# Glue.net
KiCad netlist of a schematic drawn in Altium Designer
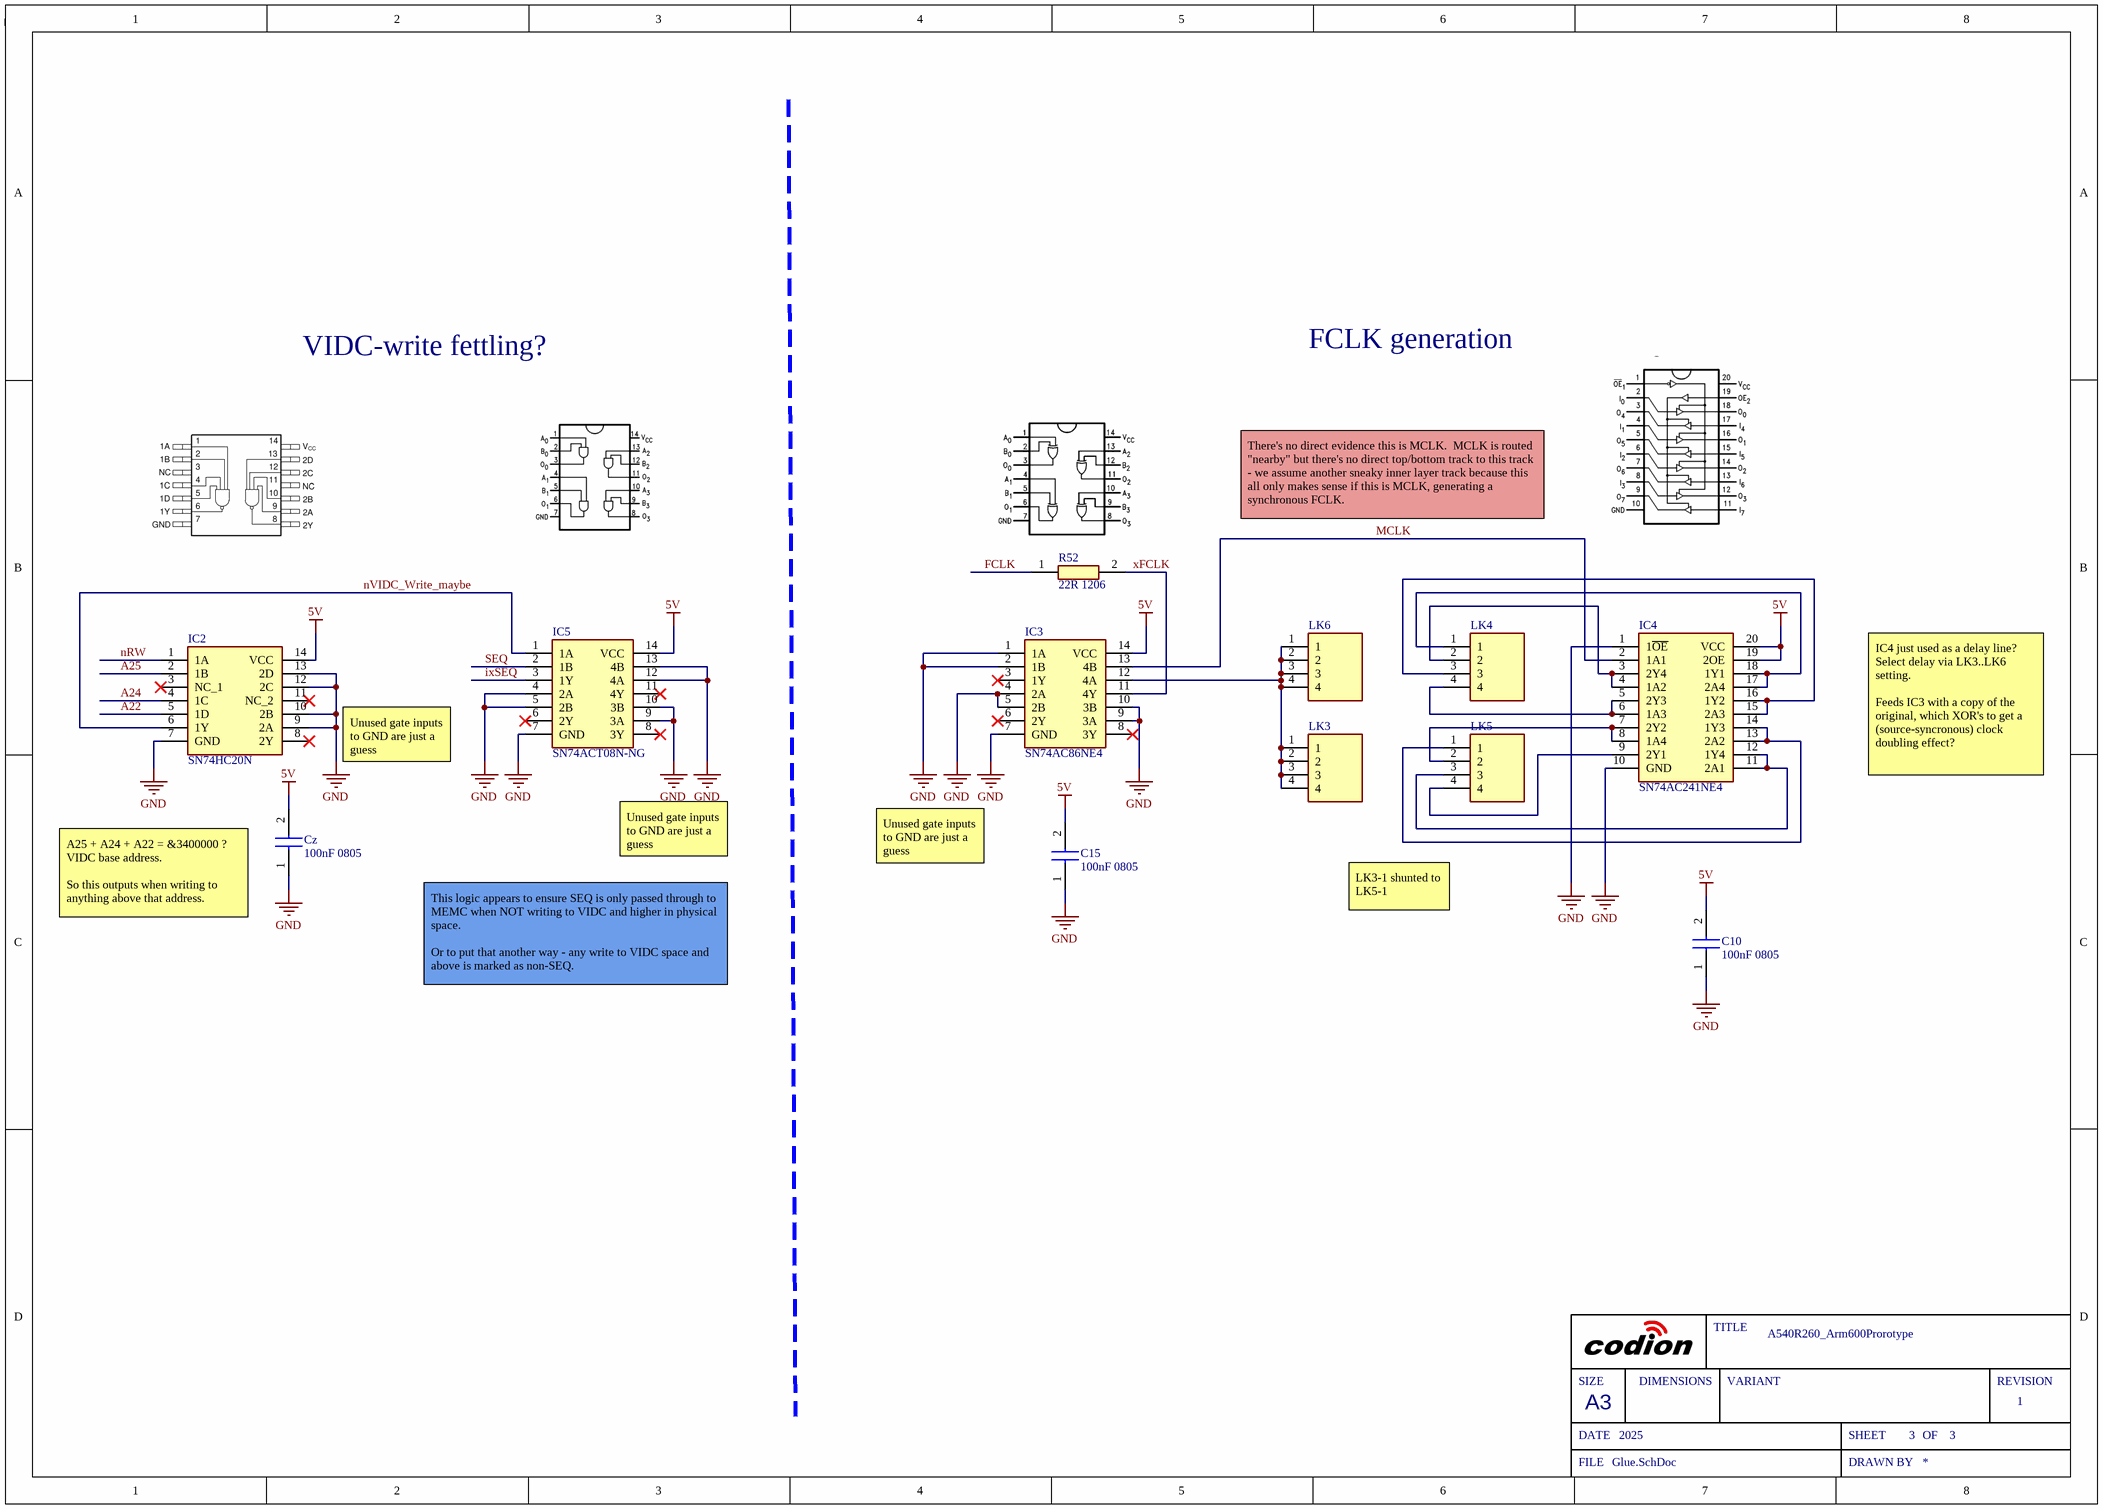
[diagram p0: Glue.SchDoc]

(export (version "E")
  (design (tool "Eeschema 10.0.6"))
  (components
    (comp (ref "C10")
      (value "100nF 0805")
      (footprint "SamacSys:CAPC2012X140N")
      (description "Capacitor")
      (fields
        (field (name "MANUFACTURER_PART_NUMBER") "C0805C104J4JACAUTO")
        (field (name "MOUSER PART NUMBER") "80-C0805C104J4JAUTO")
      )
      (libsource (lib "*") (part "C0805C104J4JACAUTO"))
    )
    (comp (ref "C15")
      (value "100nF 0805")
      (footprint "SamacSys:CAPC2012X140N")
      (description "Capacitor")
      (fields
        (field (name "MANUFACTURER_PART_NUMBER") "C0805C104J4JACAUTO")
        (field (name "MOUSER PART NUMBER") "80-C0805C104J4JAUTO")
      )
      (libsource (lib "*") (part "C0805C104J4JACAUTO"))
    )
    (comp (ref "Cz")
      (value "100nF 0805")
      (footprint "SamacSys:CAPC2012X140N")
      (description "Capacitor")
      (fields
        (field (name "MANUFACTURER_PART_NUMBER") "C0805C104J4JACAUTO")
        (field (name "MOUSER PART NUMBER") "80-C0805C104J4JAUTO")
      )
      (libsource (lib "*") (part "C0805C104J4JACAUTO"))
    )
    (comp (ref "IC2")
      (value "SN74HC20N")
      (footprint "SamacSys:DIP794W53P254L1930H508Q14N")
      (description "Integrated Circuit")
      (fields (field (name "MOUSER PART NUMBER") "595-SN74HC20N"))
      (libsource (lib "*") (part "SN74HC20N"))
    )
    (comp (ref "IC3")
      (value "SN74AC86NE4")
      (footprint "SamacSys:DIP794W53P254L1930H508Q14N")
      (description "Integrated Circuit")
      (libsource (lib "*") (part "SN74AC86NE4"))
    )
    (comp (ref "IC4")
      (value "SN74AC241NE4")
      (footprint "SamacSys:DIP794W53P254L2540H508Q20N")
      (description "Integrated Circuit")
      (libsource (lib "*") (part "SN74AC241NE4"))
    )
    (comp (ref "IC5")
      (value "SN74ACT08N-NG")
      (footprint "SamacSys:DIP794W53P254L1930H508Q14N")
      (description "Integrated Circuit")
      (libsource (lib "*") (part "SN74ACT08N-NG"))
    )
    (comp (ref "LK3")
      (value "PREC004SAAN-RC")
      (footprint "SamacSys:HDRV4W64P0X254_1X4_1016X254X854P")
      (description "Connector")
      (libsource (lib "*") (part "PREC004SAAN-RC"))
    )
    (comp (ref "LK4")
      (value "PREC004SAAN-RC")
      (footprint "SamacSys:HDRV4W64P0X254_1X4_1016X254X854P")
      (description "Connector")
      (libsource (lib "*") (part "PREC004SAAN-RC"))
    )
    (comp (ref "LK5")
      (value "PREC004SAAN-RC")
      (footprint "SamacSys:HDRV4W64P0X254_1X4_1016X254X854P")
      (description "Connector")
      (libsource (lib "*") (part "PREC004SAAN-RC"))
    )
    (comp (ref "LK6")
      (value "PREC004SAAN-RC")
      (footprint "SamacSys:HDRV4W64P0X254_1X4_1016X254X854P")
      (description "Connector")
      (libsource (lib "*") (part "PREC004SAAN-RC"))
    )
    (comp (ref "R52")
      (value "22R 1206")
      (footprint "SamacSys:ERJUP8")
      (description "Resistor")
      (fields (field (name "MANUFACTURER_PART_NUMBER") "ERJ-UP8D22R0V"))
      (libsource (lib "*") (part "ERJ-UP8D22R0V"))
    )
  )
  (nets
    (net (code "1") (name "/A22") (class "Default")
      (node (ref "IC2") (pin "5") (pinfunction "1D_5") (pintype "passive"))
    )
    (net (code "2") (name "/A24") (class "Default")
      (node (ref "IC2") (pin "4") (pinfunction "1C_4") (pintype "passive"))
    )
    (net (code "3") (name "/A25") (class "Default")
      (node (ref "IC2") (pin "2") (pinfunction "1B_2") (pintype "passive"))
    )
    (net (code "4") (name "/FCLK") (class "Default")
      (node (ref "R52") (pin "1") (pinfunction "1_1") (pintype "passive"))
    )
    (net (code "5") (name "/MCLK") (class "Default")
      (node (ref "IC3") (pin "13") (pinfunction "4B_13") (pintype "passive"))
      (node (ref "IC4") (pin "2") (pinfunction "1A1_2") (pintype "passive"))
    )
    (net (code "6") (name "/SEQ") (class "Default")
      (node (ref "IC5") (pin "2") (pinfunction "1B_2") (pintype "passive"))
    )
    (net (code "7") (name "/ixSEQ") (class "Default")
      (node (ref "IC5") (pin "3") (pinfunction "1Y_3") (pintype "passive"))
    )
    (net (code "8") (name "/nRW") (class "Default")
      (node (ref "IC2") (pin "1") (pinfunction "1A_1") (pintype "passive"))
    )
    (net (code "9") (name "/nVIDC_Write_maybe") (class "Default")
      (node (ref "IC2") (pin "6") (pinfunction "1Y_6") (pintype "passive"))
      (node (ref "IC5") (pin "1") (pinfunction "1A_1") (pintype "passive"))
    )
    (net (code "10") (name "/xFCLK") (class "Default")
      (node (ref "IC3") (pin "11") (pinfunction "4Y_11") (pintype "passive"))
      (node (ref "R52") (pin "2") (pinfunction "2_2") (pintype "passive"))
    )
    (net (code "11") (name "5V") (class "Default")
      (node (ref "C10") (pin "2") (pinfunction "2_2") (pintype "passive"))
      (node (ref "C15") (pin "2") (pinfunction "2_2") (pintype "passive"))
      (node (ref "Cz") (pin "2") (pinfunction "2_2") (pintype "passive"))
      (node (ref "IC2") (pin "14") (pinfunction "VCC_14") (pintype "passive"))
      (node (ref "IC3") (pin "14") (pinfunction "VCC_14") (pintype "passive"))
      (node (ref "IC4") (pin "19") (pinfunction "2OE_19") (pintype "passive"))
      (node (ref "IC4") (pin "20") (pinfunction "VCC_20") (pintype "passive"))
      (node (ref "IC5") (pin "14") (pinfunction "VCC_14") (pintype "passive"))
    )
    (net (code "12") (name "GND") (class "Default")
      (node (ref "C10") (pin "1") (pinfunction "1_1") (pintype "passive"))
      (node (ref "C15") (pin "1") (pinfunction "1_1") (pintype "passive"))
      (node (ref "Cz") (pin "1") (pinfunction "1_1") (pintype "passive"))
      (node (ref "IC2") (pin "10") (pinfunction "2B_10") (pintype "passive"))
      (node (ref "IC2") (pin "12") (pinfunction "2C_12") (pintype "passive"))
      (node (ref "IC2") (pin "13") (pinfunction "2D_13") (pintype "passive"))
      (node (ref "IC2") (pin "7") (pinfunction "GND_7") (pintype "passive"))
      (node (ref "IC2") (pin "9") (pinfunction "2A_9") (pintype "passive"))
      (node (ref "IC3") (pin "1") (pinfunction "1A_1") (pintype "passive"))
      (node (ref "IC3") (pin "10") (pinfunction "3B_10") (pintype "passive"))
      (node (ref "IC3") (pin "2") (pinfunction "1B_2") (pintype "passive"))
      (node (ref "IC3") (pin "4") (pinfunction "2A_4") (pintype "passive"))
      (node (ref "IC3") (pin "5") (pinfunction "2B_5") (pintype "passive"))
      (node (ref "IC3") (pin "7") (pinfunction "GND_7") (pintype "passive"))
      (node (ref "IC3") (pin "9") (pinfunction "3A_9") (pintype "passive"))
      (node (ref "IC4") (pin "1") (pinfunction "1~{OE}_1") (pintype "passive"))
      (node (ref "IC4") (pin "10") (pinfunction "GND_10") (pintype "passive"))
      (node (ref "IC5") (pin "10") (pinfunction "3B_10") (pintype "passive"))
      (node (ref "IC5") (pin "12") (pinfunction "4A_12") (pintype "passive"))
      (node (ref "IC5") (pin "13") (pinfunction "4B_13") (pintype "passive"))
      (node (ref "IC5") (pin "4") (pinfunction "2A_4") (pintype "passive"))
      (node (ref "IC5") (pin "5") (pinfunction "2B_5") (pintype "passive"))
      (node (ref "IC5") (pin "7") (pinfunction "GND_7") (pintype "passive"))
      (node (ref "IC5") (pin "9") (pinfunction "3A_9") (pintype "passive"))
    )
    (net (code "13") (name "Net-(IC3-4A)") (class "Default")
      (node (ref "IC3") (pin "12") (pinfunction "4A_12") (pintype "passive"))
      (node (ref "LK3") (pin "1") (pinfunction "1_1") (pintype "passive"))
      (node (ref "LK3") (pin "2") (pinfunction "2_2") (pintype "passive"))
      (node (ref "LK3") (pin "3") (pinfunction "3_3") (pintype "passive"))
      (node (ref "LK3") (pin "4") (pinfunction "4_4") (pintype "passive"))
      (node (ref "LK6") (pin "1") (pinfunction "1_1") (pintype "passive"))
      (node (ref "LK6") (pin "2") (pinfunction "2_2") (pintype "passive"))
      (node (ref "LK6") (pin "3") (pinfunction "3_3") (pintype "passive"))
      (node (ref "LK6") (pin "4") (pinfunction "4_4") (pintype "passive"))
    )
    (net (code "14") (name "Net-(IC4-1A2)") (class "Default")
      (node (ref "IC4") (pin "3") (pinfunction "2Y4_3") (pintype "passive"))
      (node (ref "IC4") (pin "4") (pinfunction "1A2_4") (pintype "passive"))
      (node (ref "LK4") (pin "2") (pinfunction "2_2") (pintype "passive"))
    )
    (net (code "15") (name "Net-(IC4-1A3)") (class "Default")
      (node (ref "IC4") (pin "5") (pinfunction "2Y3_5") (pintype "passive"))
      (node (ref "IC4") (pin "6") (pinfunction "1A3_6") (pintype "passive"))
      (node (ref "LK4") (pin "4") (pinfunction "4_4") (pintype "passive"))
    )
    (net (code "16") (name "Net-(IC4-1A4)") (class "Default")
      (node (ref "IC4") (pin "7") (pinfunction "2Y2_7") (pintype "passive"))
      (node (ref "IC4") (pin "8") (pinfunction "1A4_8") (pintype "passive"))
      (node (ref "LK5") (pin "2") (pinfunction "2_2") (pintype "passive"))
    )
    (net (code "17") (name "Net-(IC4-1Y1)") (class "Default")
      (node (ref "IC4") (pin "17") (pinfunction "2A4_17") (pintype "passive"))
      (node (ref "IC4") (pin "18") (pinfunction "1Y1_18") (pintype "passive"))
      (node (ref "LK4") (pin "1") (pinfunction "1_1") (pintype "passive"))
    )
    (net (code "18") (name "Net-(IC4-1Y2)") (class "Default")
      (node (ref "IC4") (pin "15") (pinfunction "2A3_15") (pintype "passive"))
      (node (ref "IC4") (pin "16") (pinfunction "1Y2_16") (pintype "passive"))
      (node (ref "LK4") (pin "3") (pinfunction "3_3") (pintype "passive"))
    )
    (net (code "19") (name "Net-(IC4-1Y3)") (class "Default")
      (node (ref "IC4") (pin "13") (pinfunction "2A2_13") (pintype "passive"))
      (node (ref "IC4") (pin "14") (pinfunction "1Y3_14") (pintype "passive"))
      (node (ref "LK5") (pin "1") (pinfunction "1_1") (pintype "passive"))
    )
    (net (code "20") (name "Net-(IC4-1Y4)") (class "Default")
      (node (ref "IC4") (pin "11") (pinfunction "2A1_11") (pintype "passive"))
      (node (ref "IC4") (pin "12") (pinfunction "1Y4_12") (pintype "passive"))
      (node (ref "LK5") (pin "3") (pinfunction "3_3") (pintype "passive"))
    )
    (net (code "21") (name "Net-(IC4-2Y1)") (class "Default")
      (node (ref "IC4") (pin "9") (pinfunction "2Y1_9") (pintype "passive"))
      (node (ref "LK5") (pin "4") (pinfunction "4_4") (pintype "passive"))
    )
    (net (code "22") (name "unconnected-(IC2-2Y-Pad8)") (class "Default")
      (node (ref "IC2") (pin "8") (pinfunction "2Y_8") (pintype "passive+no_connect"))
    )
    (net (code "23") (name "unconnected-(IC2-NC_1-Pad3)") (class "Default")
      (node (ref "IC2") (pin "3") (pinfunction "NC_1_3") (pintype "passive+no_connect"))
    )
    (net (code "24") (name "unconnected-(IC2-NC_2-Pad11)") (class "Default")
      (node (ref "IC2") (pin "11") (pinfunction "NC_2_11") (pintype "passive+no_connect"))
    )
    (net (code "25") (name "unconnected-(IC3-1Y-Pad3)") (class "Default")
      (node (ref "IC3") (pin "3") (pinfunction "1Y_3") (pintype "passive+no_connect"))
    )
    (net (code "26") (name "unconnected-(IC3-2Y-Pad6)") (class "Default")
      (node (ref "IC3") (pin "6") (pinfunction "2Y_6") (pintype "passive+no_connect"))
    )
    (net (code "27") (name "unconnected-(IC3-3Y-Pad8)") (class "Default")
      (node (ref "IC3") (pin "8") (pinfunction "3Y_8") (pintype "passive+no_connect"))
    )
    (net (code "28") (name "unconnected-(IC5-2Y-Pad6)") (class "Default")
      (node (ref "IC5") (pin "6") (pinfunction "2Y_6") (pintype "passive+no_connect"))
    )
    (net (code "29") (name "unconnected-(IC5-3Y-Pad8)") (class "Default")
      (node (ref "IC5") (pin "8") (pinfunction "3Y_8") (pintype "passive+no_connect"))
    )
    (net (code "30") (name "unconnected-(IC5-4Y-Pad11)") (class "Default")
      (node (ref "IC5") (pin "11") (pinfunction "4Y_11") (pintype "passive+no_connect"))
    )
  )
)
